# Integrated_Adapter.net
KiCad netlist of a schematic drawn in EAGLE
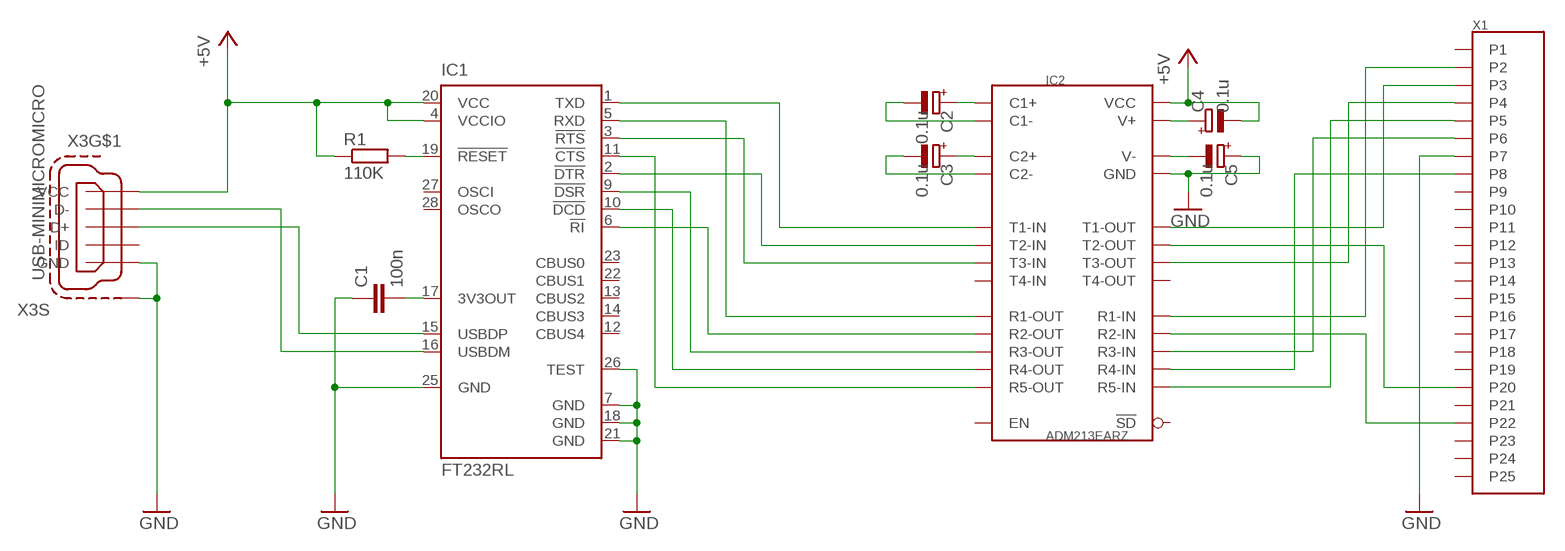
[diagram p0: schematic, sheet 1]

(export (version "E")
  (design (tool "Eeschema 10.0.6"))
  (components
    (comp (ref "C1")
      (value "100n")
      (footprint "eagle-import:CAP0805")
      (libsource (lib "eagle-import") (part "CAP_0805"))
    )
    (comp (ref "C2")
      (value "0.1u")
      (footprint "eagle-import:CAPMP3317X180")
      (libsource (lib "eagle-import") (part "CAP-POL_CAPE3216-A"))
    )
    (comp (ref "C3")
      (value "0.1u")
      (footprint "eagle-import:CAPMP3317X180")
      (libsource (lib "eagle-import") (part "CAP-POL_CAPE3216-A"))
    )
    (comp (ref "C4")
      (value "0.1u")
      (footprint "eagle-import:CAPMP3317X180")
      (libsource (lib "eagle-import") (part "CAP-POL_CAPE3216-A"))
    )
    (comp (ref "C5")
      (value "0.1u")
      (footprint "eagle-import:CAPMP3317X180")
      (libsource (lib "eagle-import") (part "CAP-POL_CAPE3216-A"))
    )
    (comp (ref "IC1")
      (value "FT232RL")
      (footprint "eagle-import:SSOP28")
      (libsource (lib "eagle-import") (part "FT232RL"))
    )
    (comp (ref "IC2")
      (value "ADM213EARZ")
      (footprint "eagle-import:SO28L")
      (libsource (lib "eagle-import") (part "ADM213EARZ"))
    )
    (comp (ref "R1")
      (value "110K")
      (footprint "eagle-import:RESC2012X50")
      (libsource (lib "eagle-import") (part "R_R0805"))
    )
    (comp (ref "X1")
      (value "DP-25")
      (footprint "eagle-import:DB-25F_SMD")
      (libsource (lib "eagle-import") (part "DP-25"))
    )
    (comp (ref "X3")
      (value "USB-MINIMICROMICRO")
      (footprint "eagle-import:USB-B-MICRO-SMD")
      (libsource (lib "eagle-import") (part "USB-MINIMICROMICRO"))
    )
  )
  (nets
    (net (code "1") (name "+5V") (class "Default")
      (node (ref "C4") (pin "2") (pinfunction "-_2") (pintype "passive"))
      (node (ref "IC1") (pin "20") (pinfunction "VCC_20") (pintype "power_in"))
      (node (ref "IC1") (pin "4") (pinfunction "VCCIO_4") (pintype "power_in"))
      (node (ref "IC2") (pin "11") (pinfunction "VCC_11") (pintype "power_in"))
      (node (ref "R1") (pin "1") (pinfunction "1_1") (pintype "passive"))
      (node (ref "X3") (pin "VBUS") (pinfunction "VCC_VBUS") (pintype "passive"))
    )
    (net (code "2") (name "GND") (class "Default")
      (node (ref "C1") (pin "1") (pinfunction "1_1") (pintype "passive"))
      (node (ref "C5") (pin "1") (pinfunction "+_1") (pintype "passive"))
      (node (ref "IC1") (pin "18") (pinfunction "GND_18") (pintype "power_in"))
      (node (ref "IC1") (pin "21") (pinfunction "GND_21") (pintype "power_in"))
      (node (ref "IC1") (pin "25") (pinfunction "GND_25") (pintype "power_in"))
      (node (ref "IC1") (pin "26") (pinfunction "TEST_26") (pintype "input"))
      (node (ref "IC1") (pin "7") (pinfunction "GND_7") (pintype "power_in"))
      (node (ref "IC2") (pin "10") (pinfunction "GND_10") (pintype "power_in"))
      (node (ref "X1") (pin "P7") (pinfunction "P7_P7") (pintype "bidirectional"))
      (node (ref "X3") (pin "GND") (pinfunction "GND_GND") (pintype "passive"))
      (node (ref "X3") (pin "SHIELD1") (pinfunction "S1_SHIELD1") (pintype "passive"))
      (node (ref "X3") (pin "SHIELD2") (pinfunction "S1_SHIELD2") (pintype "passive"))
      (node (ref "X3") (pin "SHIELD3") (pinfunction "S1_SHIELD3") (pintype "passive"))
    )
    (net (code "3") (name "Net-(C2-+)") (class "Default")
      (node (ref "C2") (pin "1") (pinfunction "+_1") (pintype "passive"))
      (node (ref "IC2") (pin "12") (pinfunction "C1+_12") (pintype "power_in"))
    )
    (net (code "4") (name "Net-(C2--)") (class "Default")
      (node (ref "C2") (pin "2") (pinfunction "-_2") (pintype "passive"))
      (node (ref "IC2") (pin "14") (pinfunction "C1-_14") (pintype "power_in"))
    )
    (net (code "5") (name "Net-(C3-+)") (class "Default")
      (node (ref "C3") (pin "1") (pinfunction "+_1") (pintype "passive"))
      (node (ref "IC2") (pin "15") (pinfunction "C2+_15") (pintype "power_in"))
    )
    (net (code "6") (name "Net-(C3--)") (class "Default")
      (node (ref "C3") (pin "2") (pinfunction "-_2") (pintype "passive"))
      (node (ref "IC2") (pin "16") (pinfunction "C2-_16") (pintype "power_in"))
    )
    (net (code "7") (name "Net-(C4-+)") (class "Default")
      (node (ref "C4") (pin "1") (pinfunction "+_1") (pintype "passive"))
      (node (ref "IC2") (pin "13") (pinfunction "V+_13") (pintype "power_in"))
    )
    (net (code "8") (name "Net-(C5--)") (class "Default")
      (node (ref "C5") (pin "2") (pinfunction "-_2") (pintype "passive"))
      (node (ref "IC2") (pin "17") (pinfunction "V-_17") (pintype "power_in"))
    )
    (net (code "9") (name "Net-(IC1-3V3OUT)") (class "Default")
      (node (ref "C1") (pin "2") (pinfunction "2_2") (pintype "passive"))
      (node (ref "IC1") (pin "17") (pinfunction "3V3OUT_17") (pintype "output"))
    )
    (net (code "10") (name "Net-(IC1-RXD)") (class "Default")
      (node (ref "IC1") (pin "5") (pinfunction "RXD_5") (pintype "input"))
      (node (ref "IC2") (pin "8") (pinfunction "R1-OUT_8") (pintype "output"))
    )
    (net (code "11") (name "Net-(IC1-TXD)") (class "Default")
      (node (ref "IC1") (pin "1") (pinfunction "TXD_1") (pintype "output"))
      (node (ref "IC2") (pin "7") (pinfunction "T1-IN_7") (pintype "input"))
    )
    (net (code "12") (name "Net-(IC1-USBDM)") (class "Default")
      (node (ref "IC1") (pin "16") (pinfunction "USBDM_16") (pintype "bidirectional"))
      (node (ref "X3") (pin "D-") (pinfunction "D-_D-") (pintype "passive"))
    )
    (net (code "13") (name "Net-(IC1-USBDP)") (class "Default")
      (node (ref "IC1") (pin "15") (pinfunction "USBDP_15") (pintype "bidirectional"))
      (node (ref "X3") (pin "D+") (pinfunction "D+_D+") (pintype "passive"))
    )
    (net (code "14") (name "Net-(IC1-~{CTS})") (class "Default")
      (node (ref "IC1") (pin "11") (pinfunction "~{CTS}_11") (pintype "input"))
      (node (ref "IC2") (pin "19") (pinfunction "R5-OUT_19") (pintype "output"))
    )
    (net (code "15") (name "Net-(IC1-~{DCD})") (class "Default")
      (node (ref "IC1") (pin "10") (pinfunction "~{DCD}_10") (pintype "input"))
      (node (ref "IC2") (pin "22") (pinfunction "R4-OUT_22") (pintype "output"))
    )
    (net (code "16") (name "Net-(IC1-~{DSR})") (class "Default")
      (node (ref "IC1") (pin "9") (pinfunction "~{DSR}_9") (pintype "input"))
      (node (ref "IC2") (pin "26") (pinfunction "R3-OUT_26") (pintype "output"))
    )
    (net (code "17") (name "Net-(IC1-~{DTR})") (class "Default")
      (node (ref "IC1") (pin "2") (pinfunction "~{DTR}_2") (pintype "output"))
      (node (ref "IC2") (pin "6") (pinfunction "T2-IN_6") (pintype "input"))
    )
    (net (code "18") (name "Net-(IC1-~{RESET})") (class "Default")
      (node (ref "IC1") (pin "19") (pinfunction "~{RESET}_19") (pintype "input"))
      (node (ref "R1") (pin "2") (pinfunction "2_2") (pintype "passive"))
    )
    (net (code "19") (name "Net-(IC1-~{RI})") (class "Default")
      (node (ref "IC1") (pin "6") (pinfunction "~{RI}_6") (pintype "input"))
      (node (ref "IC2") (pin "5") (pinfunction "R2-OUT_5") (pintype "output"))
    )
    (net (code "20") (name "Net-(IC1-~{RTS})") (class "Default")
      (node (ref "IC1") (pin "3") (pinfunction "~{RTS}_3") (pintype "output"))
      (node (ref "IC2") (pin "20") (pinfunction "T3-IN_20") (pintype "input"))
    )
    (net (code "21") (name "Net-(IC2-R1-IN)") (class "Default")
      (node (ref "IC2") (pin "9") (pinfunction "R1-IN_9") (pintype "input"))
      (node (ref "X1") (pin "P2") (pinfunction "P2_P2") (pintype "bidirectional"))
    )
    (net (code "22") (name "Net-(IC2-R2-IN)") (class "Default")
      (node (ref "IC2") (pin "4") (pinfunction "R2-IN_4") (pintype "input"))
      (node (ref "X1") (pin "P22") (pinfunction "P22_P22") (pintype "bidirectional"))
    )
    (net (code "23") (name "Net-(IC2-R3-IN)") (class "Default")
      (node (ref "IC2") (pin "27") (pinfunction "R3-IN_27") (pintype "input"))
      (node (ref "X1") (pin "P6") (pinfunction "P6_P6") (pintype "bidirectional"))
    )
    (net (code "24") (name "Net-(IC2-R4-IN)") (class "Default")
      (node (ref "IC2") (pin "23") (pinfunction "R4-IN_23") (pintype "input"))
      (node (ref "X1") (pin "P8") (pinfunction "P8_P8") (pintype "bidirectional"))
    )
    (net (code "25") (name "Net-(IC2-R5-IN)") (class "Default")
      (node (ref "IC2") (pin "18") (pinfunction "R5-IN_18") (pintype "input"))
      (node (ref "X1") (pin "P5") (pinfunction "P5_P5") (pintype "bidirectional"))
    )
    (net (code "26") (name "Net-(IC2-T1-OUT)") (class "Default")
      (node (ref "IC2") (pin "2") (pinfunction "T1-OUT_2") (pintype "output"))
      (node (ref "X1") (pin "P3") (pinfunction "P3_P3") (pintype "bidirectional"))
    )
    (net (code "27") (name "Net-(IC2-T2-OUT)") (class "Default")
      (node (ref "IC2") (pin "3") (pinfunction "T2-OUT_3") (pintype "output"))
      (node (ref "X1") (pin "P20") (pinfunction "P20_P20") (pintype "bidirectional"))
    )
    (net (code "28") (name "Net-(IC2-T3-OUT)") (class "Default")
      (node (ref "IC2") (pin "1") (pinfunction "T3-OUT_1") (pintype "output"))
      (node (ref "X1") (pin "P4") (pinfunction "P4_P4") (pintype "bidirectional"))
    )
    (net (code "29") (name "unconnected-(IC1-CBUS0-Pad23)") (class "Default")
      (node (ref "IC1") (pin "23") (pinfunction "CBUS0_23") (pintype "bidirectional"))
    )
    (net (code "30") (name "unconnected-(IC1-CBUS1-Pad22)") (class "Default")
      (node (ref "IC1") (pin "22") (pinfunction "CBUS1_22") (pintype "bidirectional"))
    )
    (net (code "31") (name "unconnected-(IC1-CBUS2-Pad13)") (class "Default")
      (node (ref "IC1") (pin "13") (pinfunction "CBUS2_13") (pintype "bidirectional"))
    )
    (net (code "32") (name "unconnected-(IC1-CBUS3-Pad14)") (class "Default")
      (node (ref "IC1") (pin "14") (pinfunction "CBUS3_14") (pintype "bidirectional"))
    )
    (net (code "33") (name "unconnected-(IC1-CBUS4-Pad12)") (class "Default")
      (node (ref "IC1") (pin "12") (pinfunction "CBUS4_12") (pintype "bidirectional"))
    )
    (net (code "34") (name "unconnected-(IC1-OSCI-Pad27)") (class "Default")
      (node (ref "IC1") (pin "27") (pinfunction "OSCI_27") (pintype "input"))
    )
    (net (code "35") (name "unconnected-(IC1-OSCO-Pad28)") (class "Default")
      (node (ref "IC1") (pin "28") (pinfunction "OSCO_28") (pintype "output"))
    )
    (net (code "36") (name "unconnected-(IC2-EN-Pad24)") (class "Default")
      (node (ref "IC2") (pin "24") (pinfunction "EN_24") (pintype "input"))
    )
    (net (code "37") (name "unconnected-(IC2-T4-IN-Pad21)") (class "Default")
      (node (ref "IC2") (pin "21") (pinfunction "T4-IN_21") (pintype "input"))
    )
    (net (code "38") (name "unconnected-(IC2-T4-OUT-Pad28)") (class "Default")
      (node (ref "IC2") (pin "28") (pinfunction "T4-OUT_28") (pintype "output"))
    )
    (net (code "39") (name "unconnected-(IC2-~{SD}-Pad25)") (class "Default")
      (node (ref "IC2") (pin "25") (pinfunction "~{SD}_25") (pintype "input"))
    )
    (net (code "40") (name "unconnected-(X1-PadP1)") (class "Default")
      (node (ref "X1") (pin "P1") (pinfunction "P1_P1") (pintype "bidirectional"))
    )
    (net (code "41") (name "unconnected-(X1-PadP9)") (class "Default")
      (node (ref "X1") (pin "P9") (pinfunction "P9_P9") (pintype "bidirectional"))
    )
    (net (code "42") (name "unconnected-(X1-PadP10)") (class "Default")
      (node (ref "X1") (pin "P10") (pinfunction "P10_P10") (pintype "bidirectional"))
    )
    (net (code "43") (name "unconnected-(X1-PadP11)") (class "Default")
      (node (ref "X1") (pin "P11") (pinfunction "P11_P11") (pintype "bidirectional"))
    )
    (net (code "44") (name "unconnected-(X1-PadP12)") (class "Default")
      (node (ref "X1") (pin "P12") (pinfunction "P12_P12") (pintype "bidirectional"))
    )
    (net (code "45") (name "unconnected-(X1-PadP13)") (class "Default")
      (node (ref "X1") (pin "P13") (pinfunction "P13_P13") (pintype "bidirectional"))
    )
    (net (code "46") (name "unconnected-(X1-PadP14)") (class "Default")
      (node (ref "X1") (pin "P14") (pinfunction "P14_P14") (pintype "bidirectional"))
    )
    (net (code "47") (name "unconnected-(X1-PadP15)") (class "Default")
      (node (ref "X1") (pin "P15") (pinfunction "P15_P15") (pintype "bidirectional"))
    )
    (net (code "48") (name "unconnected-(X1-PadP16)") (class "Default")
      (node (ref "X1") (pin "P16") (pinfunction "P16_P16") (pintype "bidirectional"))
    )
    (net (code "49") (name "unconnected-(X1-PadP17)") (class "Default")
      (node (ref "X1") (pin "P17") (pinfunction "P17_P17") (pintype "bidirectional"))
    )
    (net (code "50") (name "unconnected-(X1-PadP18)") (class "Default")
      (node (ref "X1") (pin "P18") (pinfunction "P18_P18") (pintype "bidirectional"))
    )
    (net (code "51") (name "unconnected-(X1-PadP19)") (class "Default")
      (node (ref "X1") (pin "P19") (pinfunction "P19_P19") (pintype "bidirectional"))
    )
    (net (code "52") (name "unconnected-(X1-PadP21)") (class "Default")
      (node (ref "X1") (pin "P21") (pinfunction "P21_P21") (pintype "bidirectional"))
    )
    (net (code "53") (name "unconnected-(X1-PadP23)") (class "Default")
      (node (ref "X1") (pin "P23") (pinfunction "P23_P23") (pintype "bidirectional"))
    )
    (net (code "54") (name "unconnected-(X1-PadP24)") (class "Default")
      (node (ref "X1") (pin "P24") (pinfunction "P24_P24") (pintype "bidirectional"))
    )
    (net (code "55") (name "unconnected-(X1-PadP25)") (class "Default")
      (node (ref "X1") (pin "P25") (pinfunction "P25_P25") (pintype "bidirectional"))
    )
    (net (code "56") (name "unconnected-(X3-PadID)") (class "Default")
      (node (ref "X3") (pin "ID") (pinfunction "ID_ID") (pintype "passive"))
    )
  )
)
